# RMP_-_HALF_BRIDGE_0_0_2.net
KiCad netlist of a schematic drawn in EAGLE
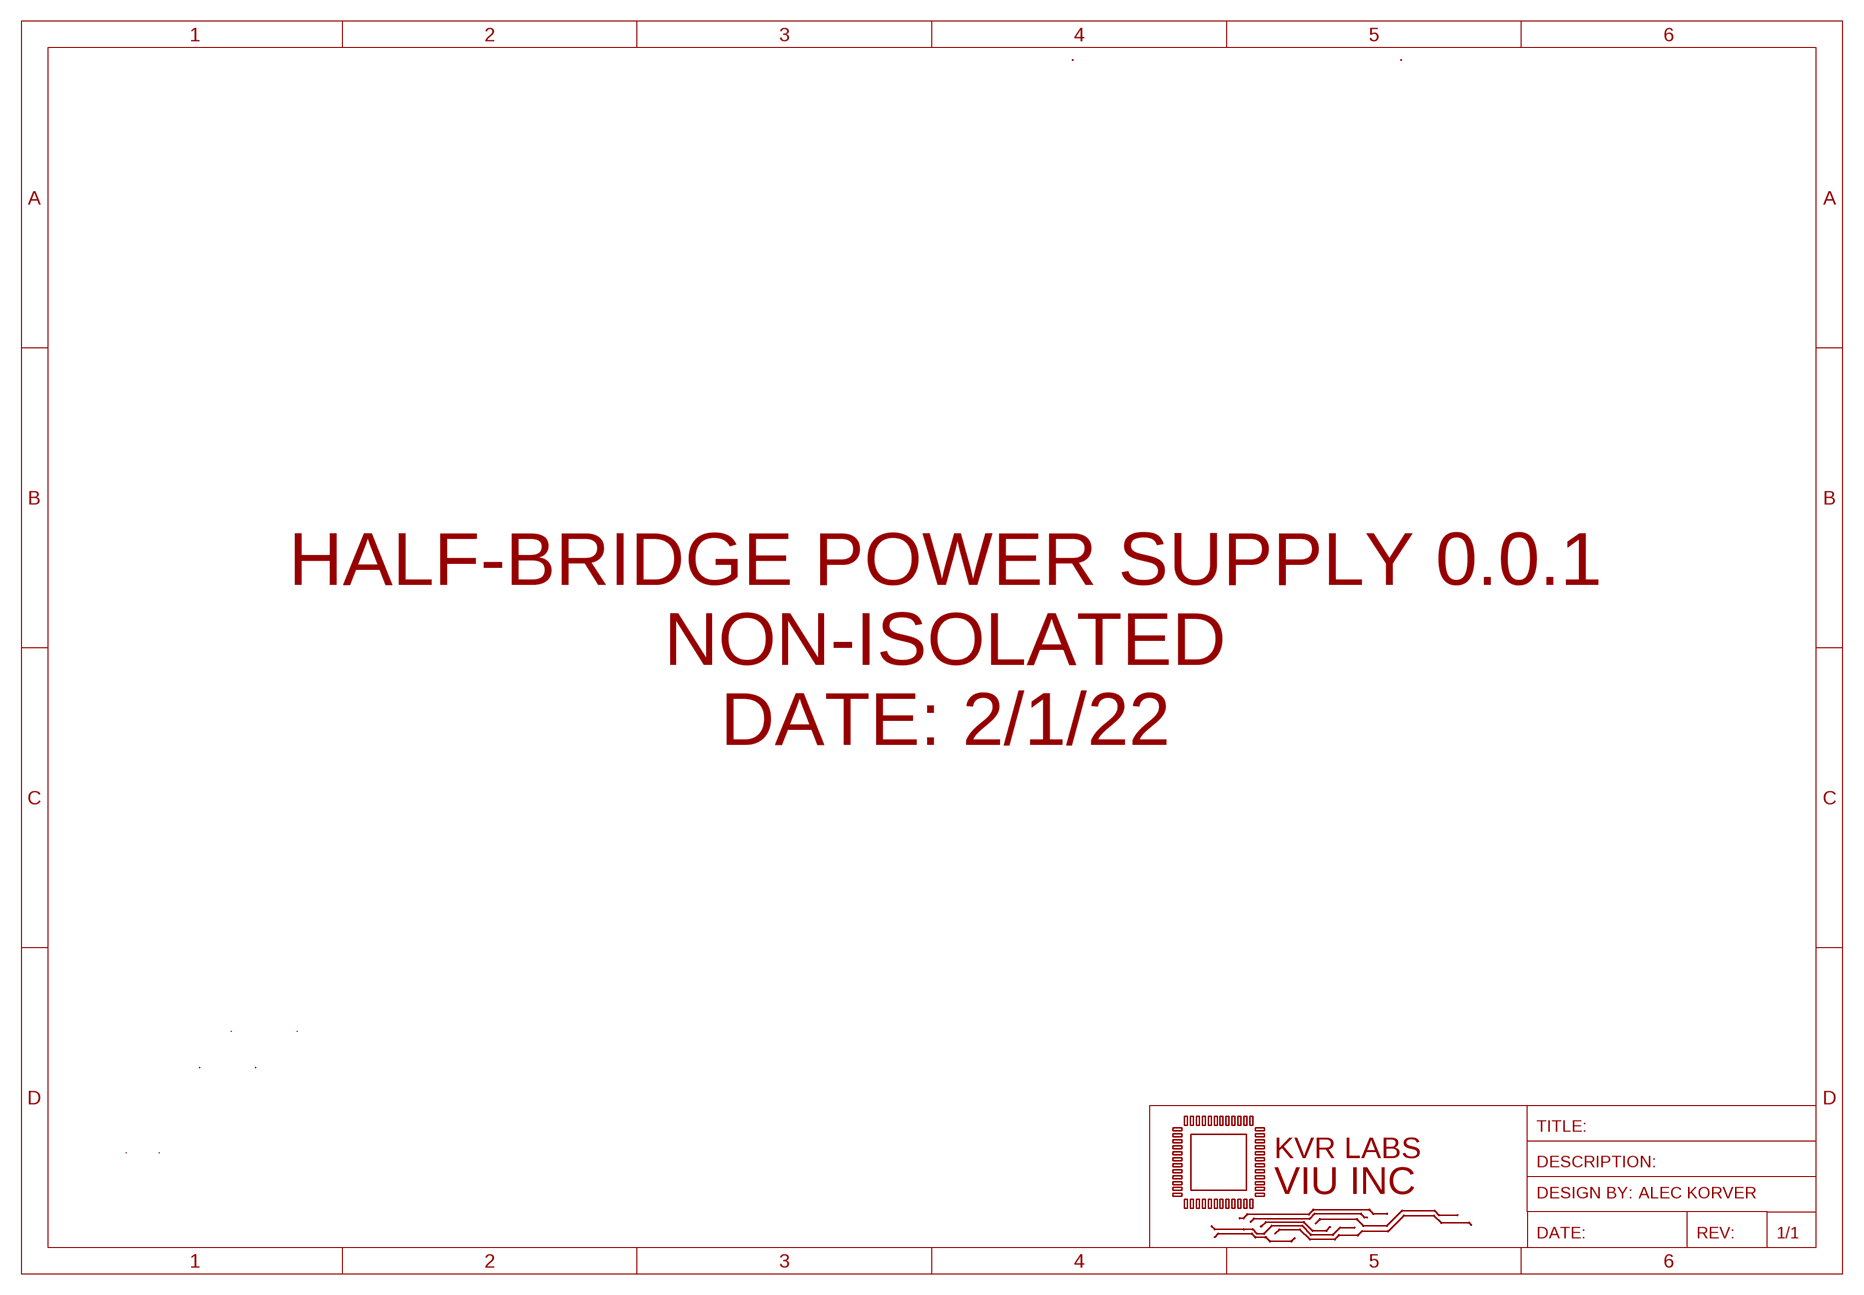
[diagram p0: schematic, sheet 1]
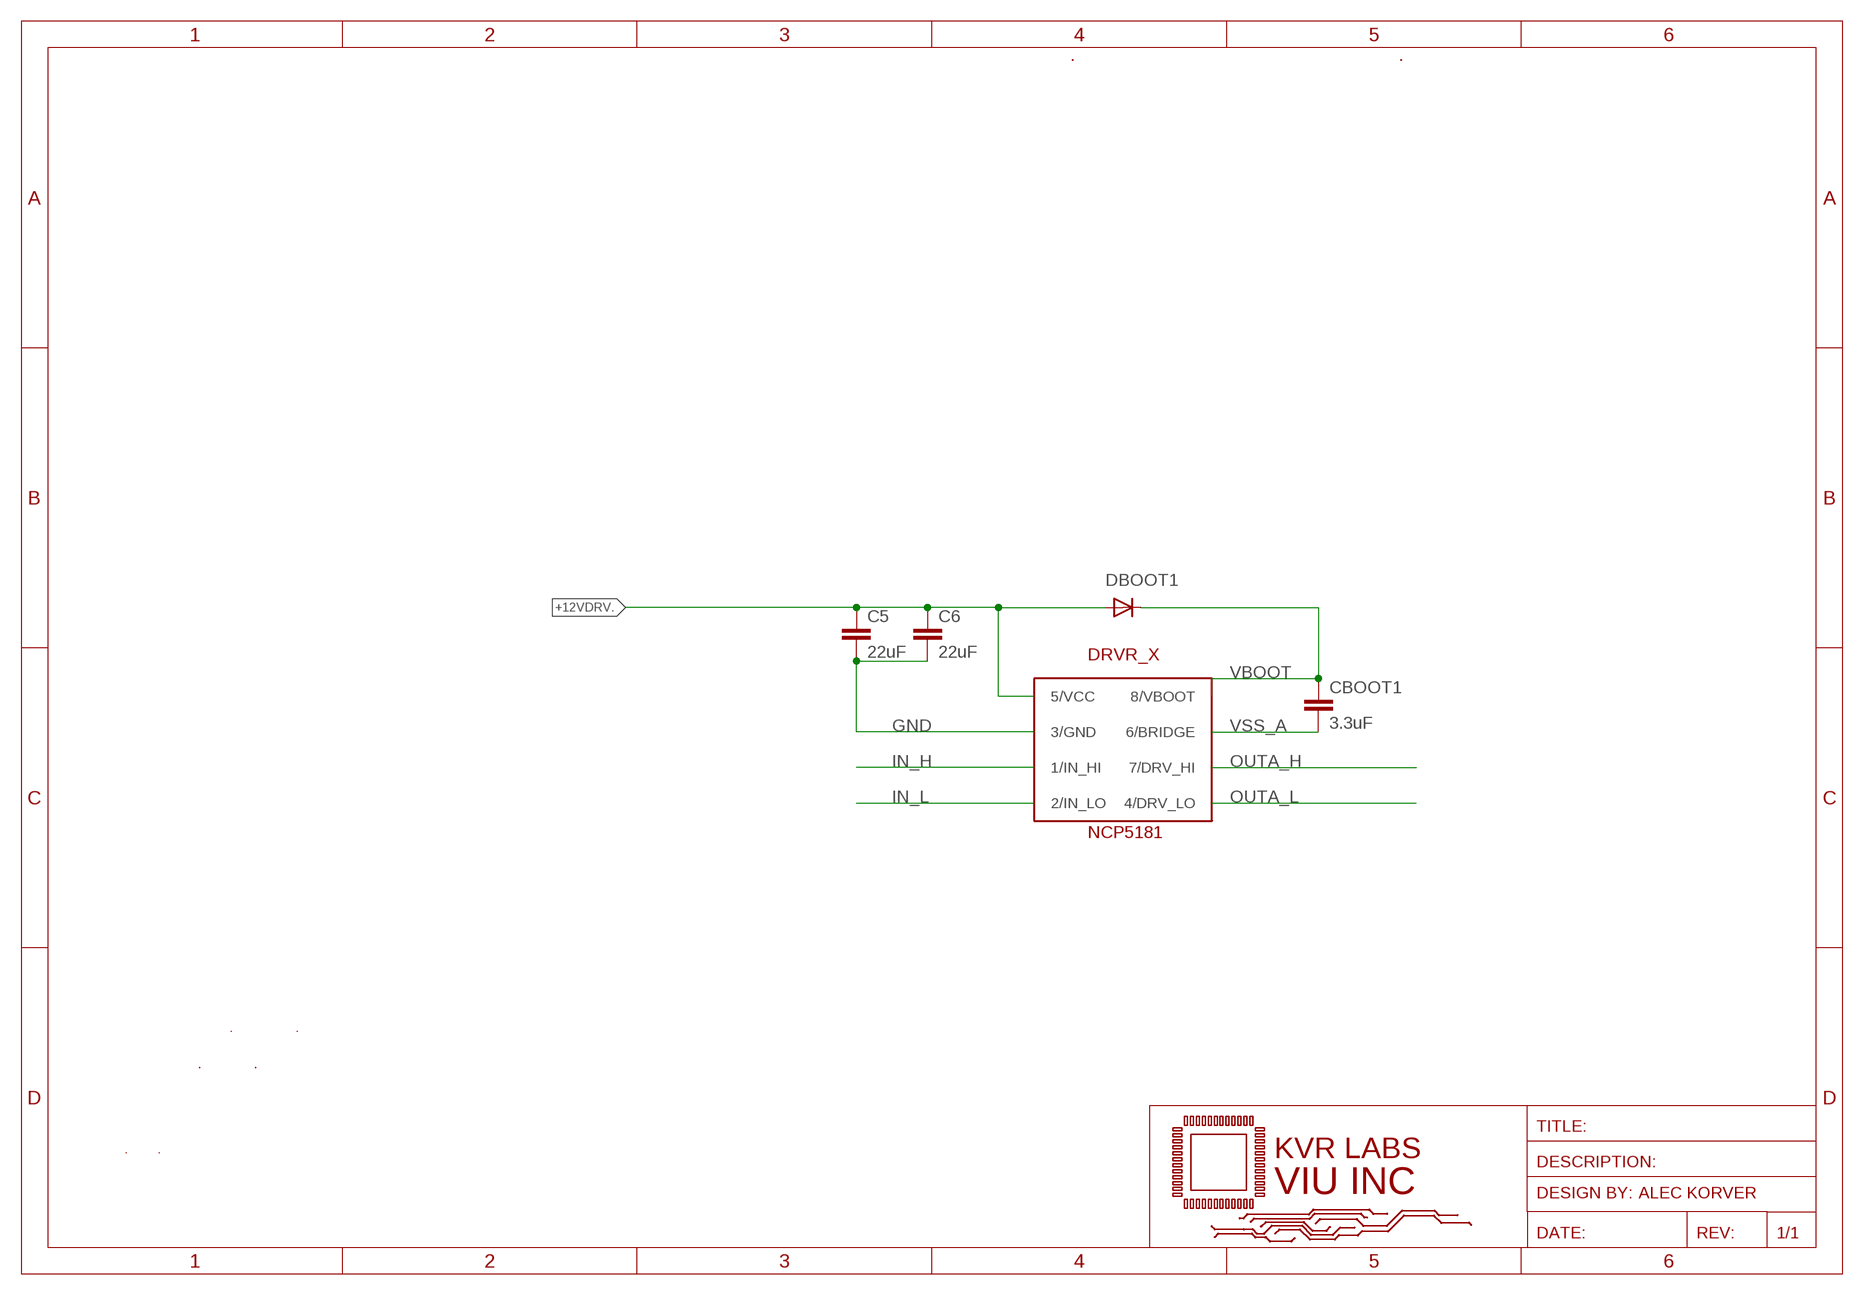
[diagram p1: schematic, sheet 2]
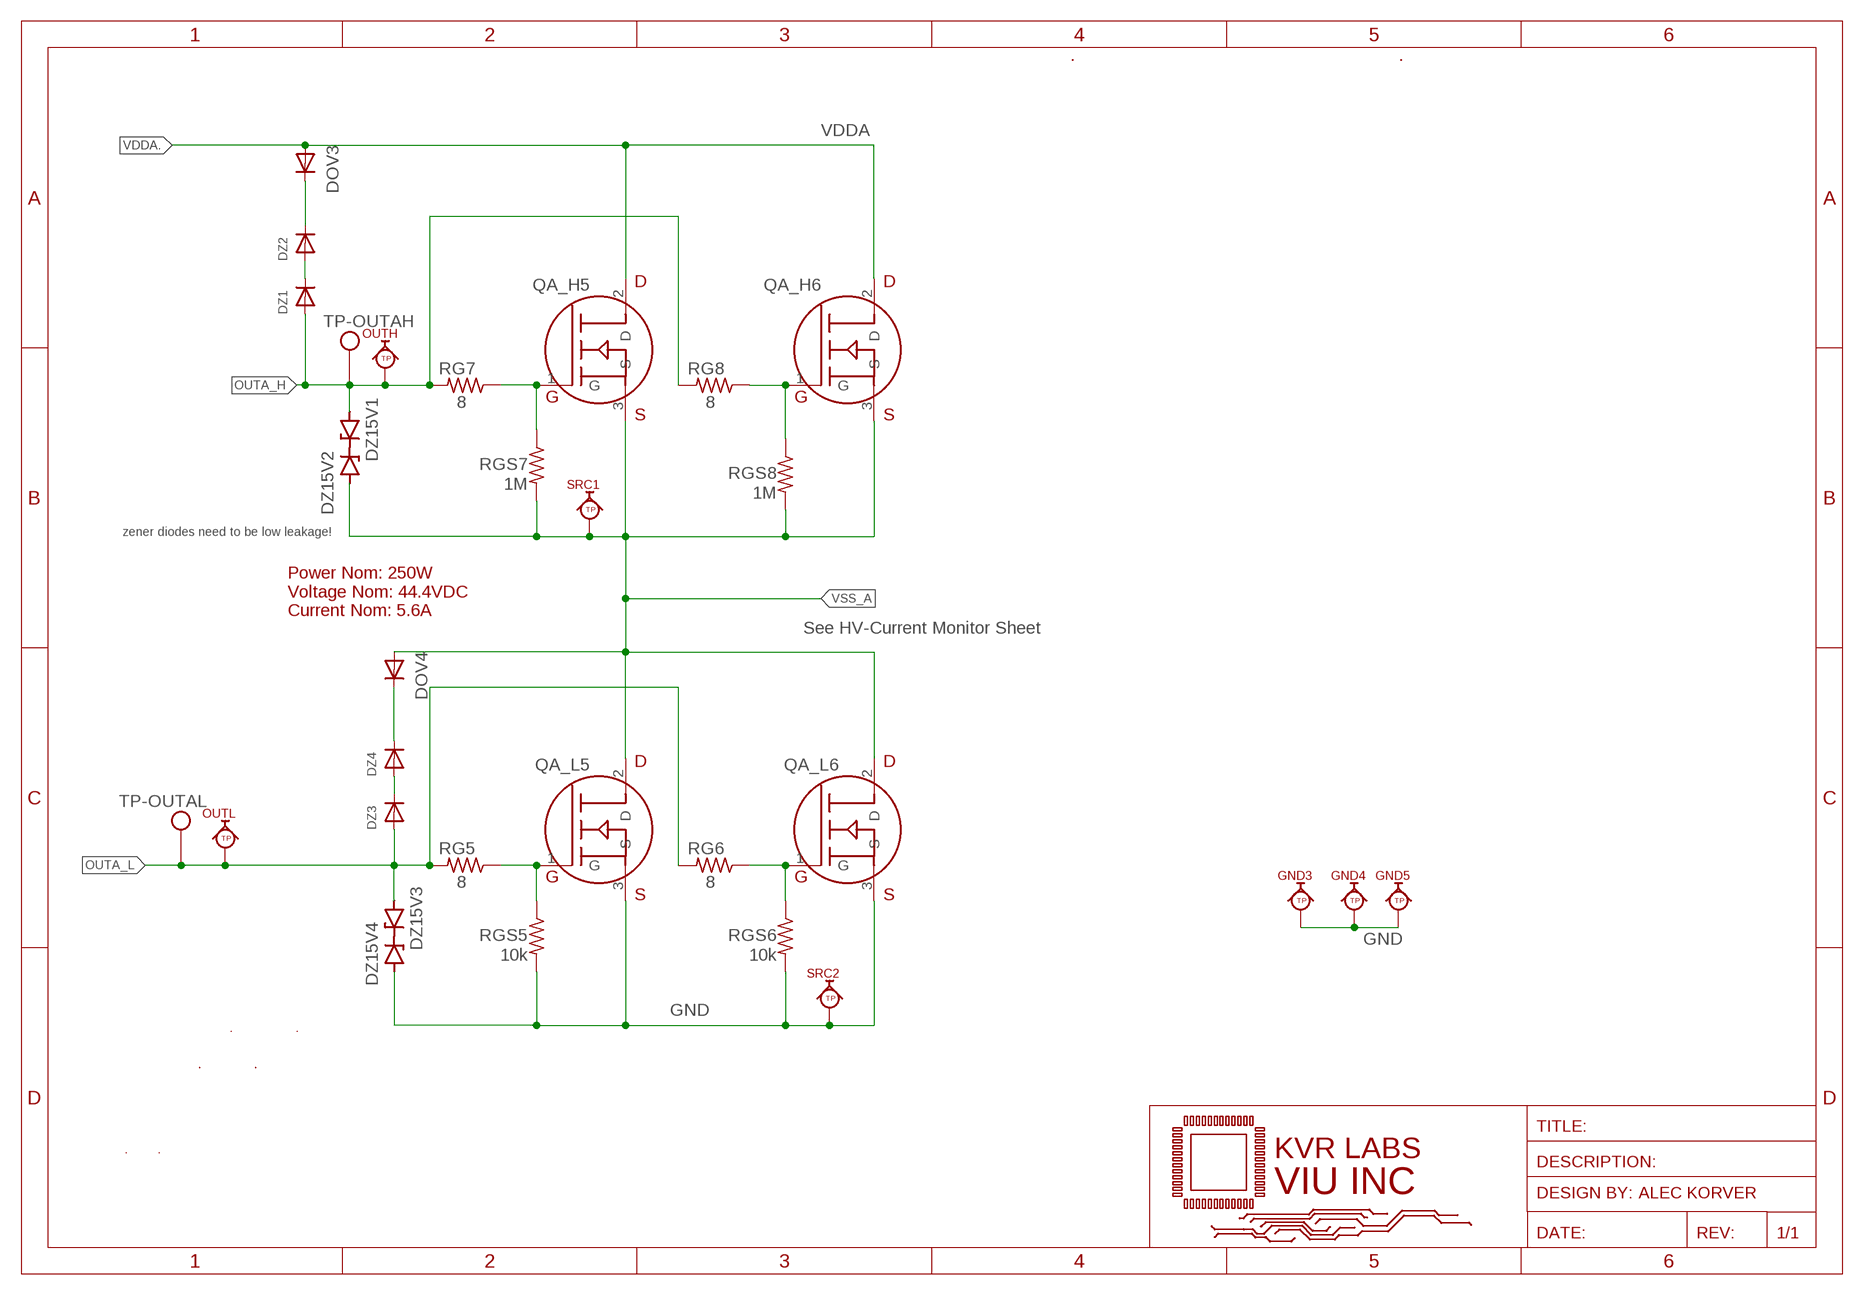
[diagram p2: schematic, sheet 3]
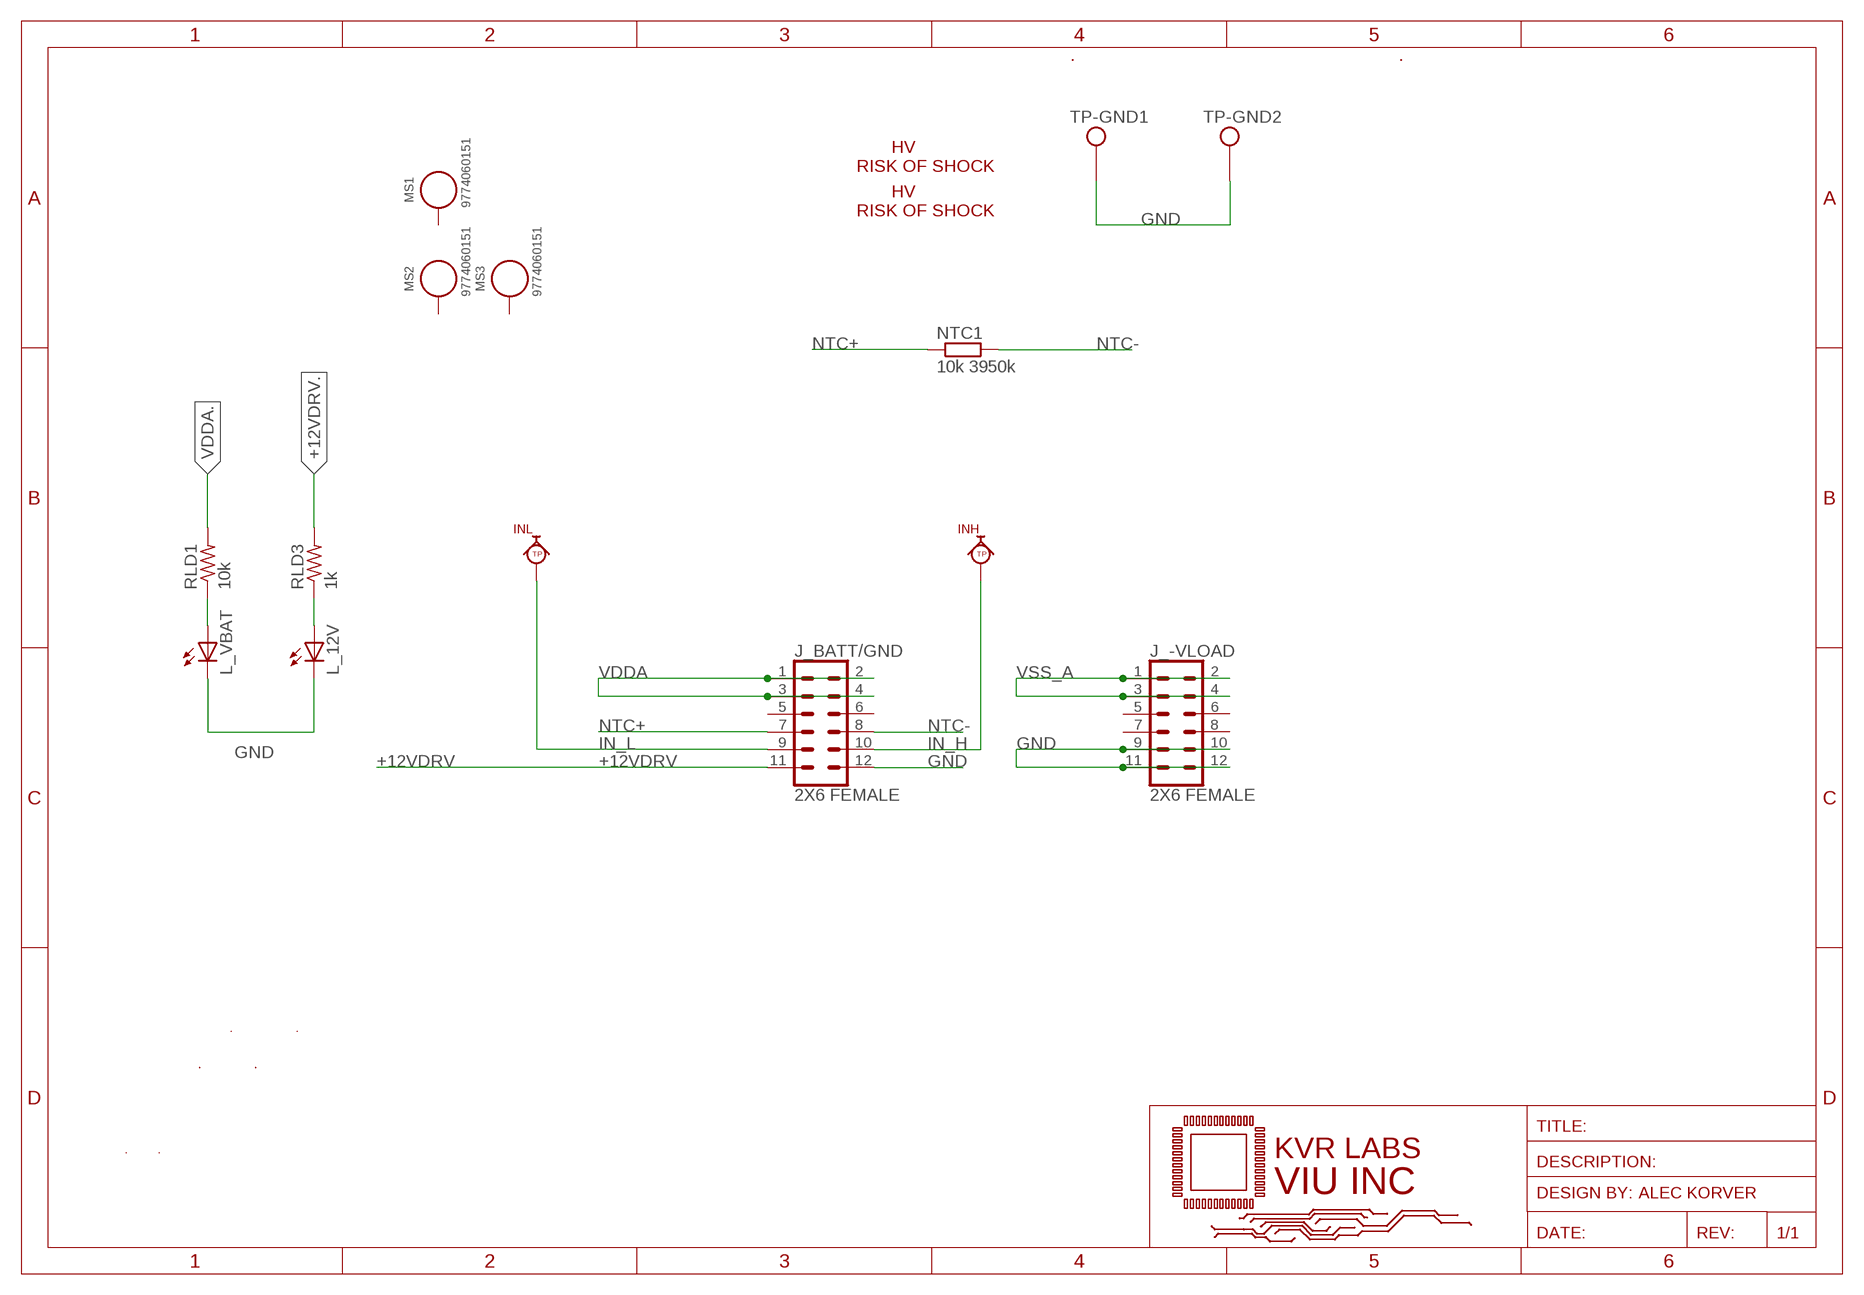
[diagram p3: schematic, sheet 4]
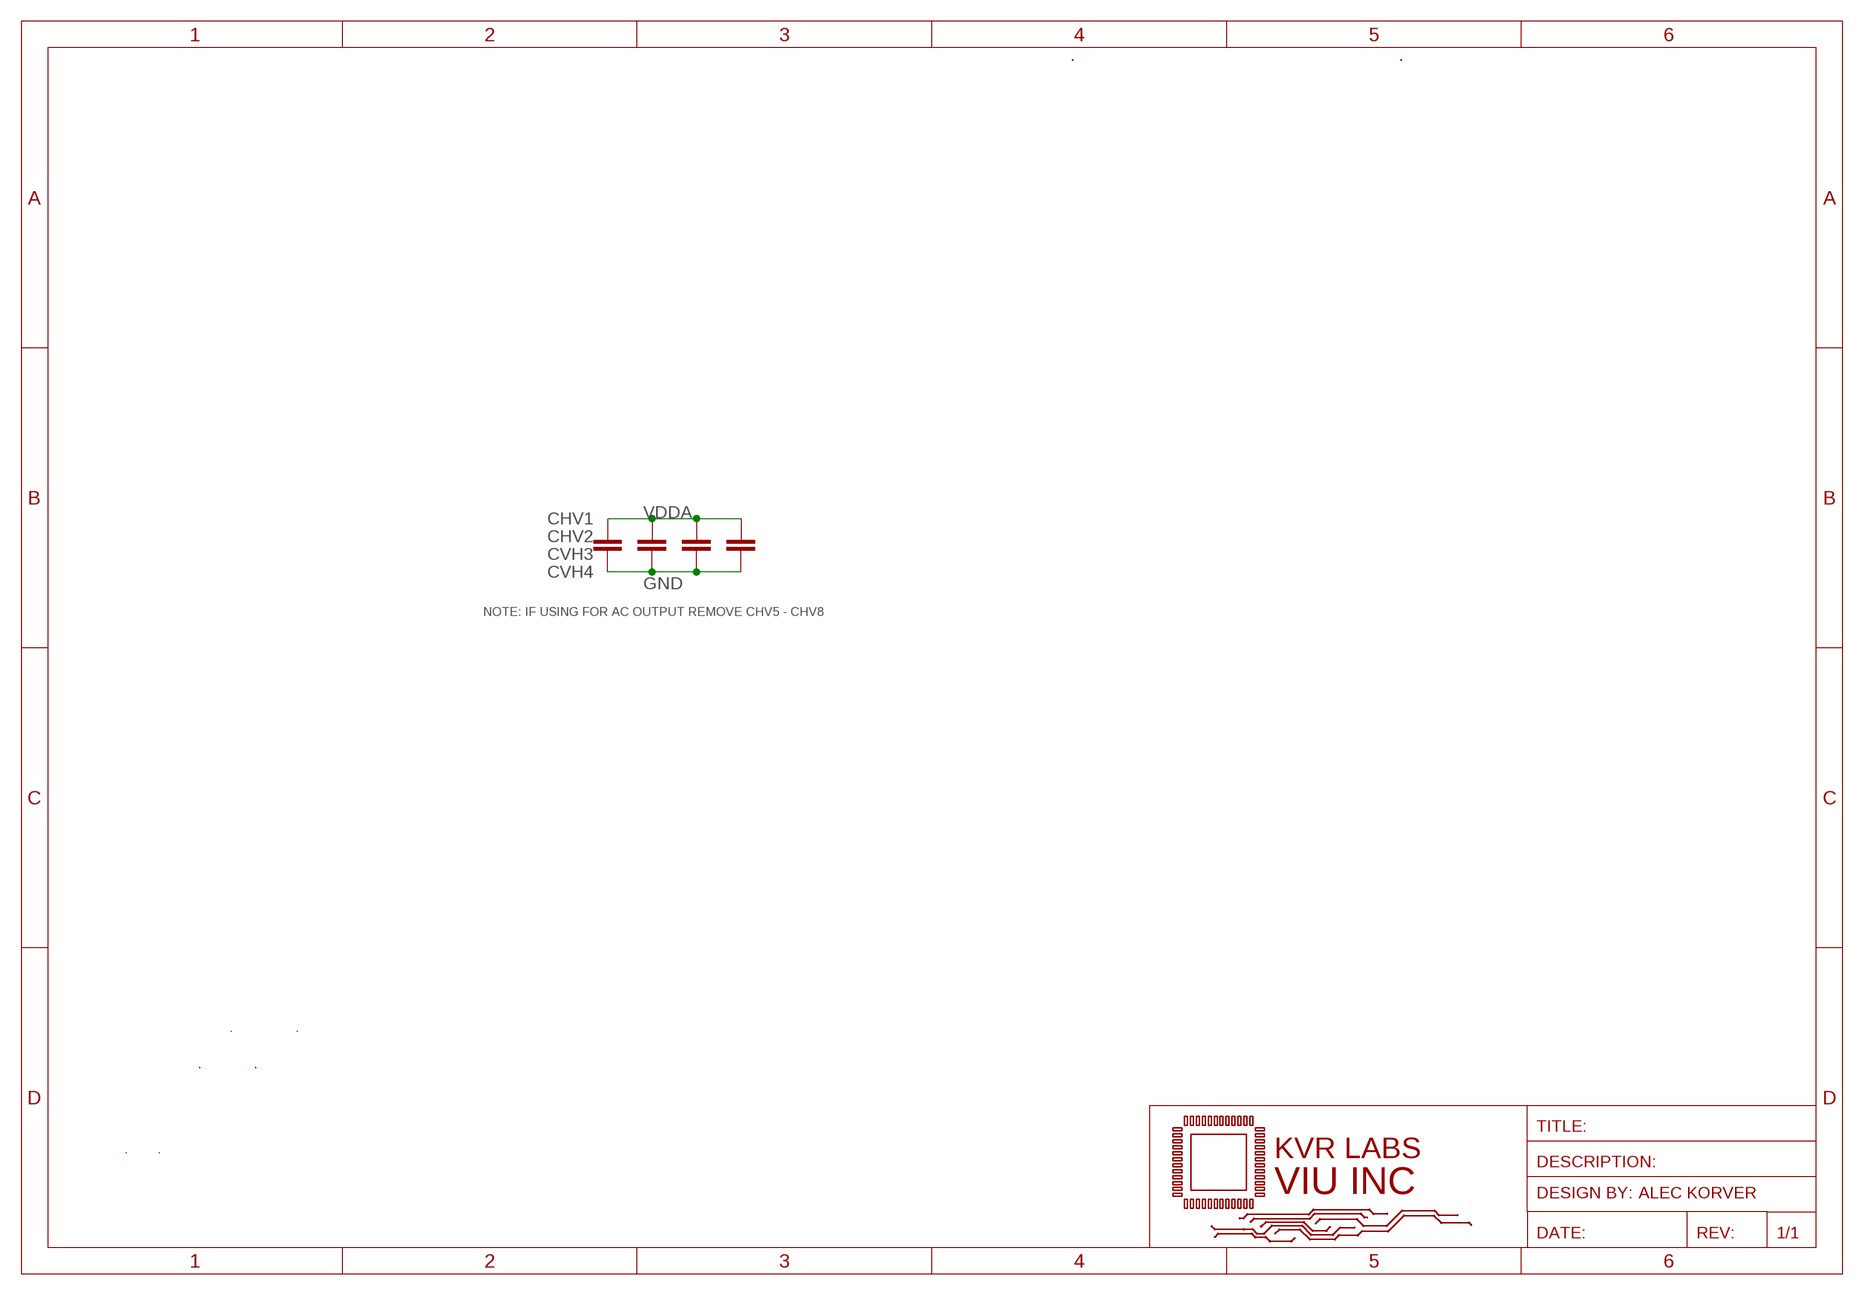
[diagram p4: schematic, sheet 5]

(export (version "E")
  (design (tool "Eeschema 10.0.6"))
  (components
    (comp (ref "CHV1")
      (value "3.3uF, 100V")
      (footprint "eagle-import:C2220K")
      (fields (field (name "LCSC_PART") "DNP/C342270"))
      (libsource (lib "eagle-import") (part "C-EUC2220K"))
    )
    (comp (ref "CHV2")
      (value "3.3uF, 100V")
      (footprint "eagle-import:C2220K")
      (fields (field (name "LCSC_PART") "DNP/C342270"))
      (libsource (lib "eagle-import") (part "C-EUC2220K"))
    )
    (comp (ref "CVH3")
      (value "3.3uF, 100V")
      (footprint "eagle-import:C2220K")
      (fields (field (name "LCSC_PART") "DNP/C342270"))
      (libsource (lib "eagle-import") (part "C-EUC2220K"))
    )
    (comp (ref "CVH4")
      (value "3.3uF, 100V")
      (footprint "eagle-import:C2220K")
      (fields (field (name "LCSC_PART") "DNP/C342270"))
      (libsource (lib "eagle-import") (part "C-EUC2220K"))
    )
    (comp (ref "INH")
      (value "KEYSTONE_5190_SMT")
      (footprint "eagle-import:KEYSTONE_5190_SMT")
      (libsource (lib "eagle-import") (part "KEYSTONE_5190_SMT"))
    )
    (comp (ref "INL")
      (value "KEYSTONE_5190_SMT")
      (footprint "eagle-import:KEYSTONE_5190_SMT")
      (libsource (lib "eagle-import") (part "KEYSTONE_5190_SMT"))
    )
    (comp (ref "J_-VLOAD")
      (value "2X6 FEMALE")
      (footprint "eagle-import:2X6")
      (fields (field (name "LCSC_PART") "DNP"))
      (libsource (lib "eagle-import") (part "CONN_06X2PTH_FEMALE"))
    )
    (comp (ref "J_BATT/GND")
      (value "2X6 FEMALE")
      (footprint "eagle-import:2X6")
      (fields (field (name "LCSC_PART") "DNP"))
      (libsource (lib "eagle-import") (part "CONN_06X2PTH_FEMALE"))
    )
    (comp (ref "L_12V")
      (value "LEDCHIPLED_1206")
      (footprint "eagle-import:CHIPLED_1206")
      (fields (field (name "LCSC_PART") "C434439"))
      (libsource (lib "eagle-import") (part "LEDCHIPLED_1206"))
    )
    (comp (ref "L_VBAT")
      (value "LEDCHIPLED_1206")
      (footprint "eagle-import:CHIPLED_1206")
      (fields (field (name "LCSC_PART") "C434439"))
      (libsource (lib "eagle-import") (part "LEDCHIPLED_1206"))
    )
    (comp (ref "MS1")
      (value "9774060151")
      (footprint "eagle-import:WA-SMSI_9774060151")
      (fields (field (name "LCSC_PART") "DNP"))
      (libsource (lib "eagle-import") (part "WA-SMSI_9774XXX151_9774060151"))
    )
    (comp (ref "MS2")
      (value "9774060151")
      (footprint "eagle-import:WA-SMSI_9774060151")
      (fields (field (name "LCSC_PART") "DNP"))
      (libsource (lib "eagle-import") (part "WA-SMSI_9774XXX151_9774060151"))
    )
    (comp (ref "MS3")
      (value "9774060151")
      (footprint "eagle-import:WA-SMSI_9774060151")
      (fields (field (name "LCSC_PART") "DNP"))
      (libsource (lib "eagle-import") (part "WA-SMSI_9774XXX151_9774060151"))
    )
    (comp (ref "NTC1")
      (value "10k 3950k")
      (footprint "eagle-import:R0805")
      (fields (field (name "LCSC_PART") "C95968"))
      (libsource (lib "eagle-import") (part "R-EU_R0805"))
    )
    (comp (ref "RLD1")
      (value "10k")
      (footprint "eagle-import:R1206")
      (fields (field (name "LCSC_PART") "C140407"))
      (libsource (lib "eagle-import") (part "R-US_R1206"))
    )
    (comp (ref "RLD3")
      (value "1k")
      (footprint "eagle-import:R1206")
      (fields (field (name "LCSC_PART") "C115421"))
      (libsource (lib "eagle-import") (part "R-US_R1206"))
    )
    (comp (ref "TP-GND1")
      (value "THM_TESTPOINT_5000_SERIES")
      (footprint "eagle-import:THM-TESTPOINT")
      (fields (field (name "LCSC_PART") "DNP"))
      (libsource (lib "eagle-import") (part "THM_TESTPOINT_5000_SERIES"))
    )
    (comp (ref "TP-GND2")
      (value "THM_TESTPOINT_5000_SERIES")
      (footprint "eagle-import:THM-TESTPOINT")
      (fields (field (name "LCSC_PART") "DNP"))
      (libsource (lib "eagle-import") (part "THM_TESTPOINT_5000_SERIES"))
    )
    (comp (ref "U$10")
      (value "ELECTRIC_SHOCK")
      (footprint "eagle-import:ELECTRIC_SHOCK")
      (fields (field (name "LCSC_PART") "DNP"))
      (libsource (lib "eagle-import") (part "ELECTRIC_SHOCK"))
    )
    (comp (ref "U$11")
      (value "ELECTRIC_SHOCK")
      (footprint "eagle-import:ELECTRIC_SHOCK")
      (fields (field (name "LCSC_PART") "DNP"))
      (libsource (lib "eagle-import") (part "ELECTRIC_SHOCK"))
    )
    (comp (ref "C5")
      (value "22uF")
      (footprint "eagle-import:C1206")
      (fields (field (name "LCSC_PART") "C77091"))
      (libsource (lib "eagle-import") (part "C-EUC1206"))
    )
    (comp (ref "C6")
      (value "22uF")
      (footprint "eagle-import:C1206")
      (fields (field (name "LCSC_PART") "C77091"))
      (libsource (lib "eagle-import") (part "C-EUC1206"))
    )
    (comp (ref "CBOOT1")
      (value "3.3uF")
      (footprint "eagle-import:C1812")
      (fields (field (name "LCSC_PART") "C342636"))
      (libsource (lib "eagle-import") (part "C-EUC1812"))
    )
    (comp (ref "DBOOT1")
      (value "DIODESMA")
      (footprint "eagle-import:SMADIODE")
      (fields (field (name "LCSC_PART") "C110531"))
      (libsource (lib "eagle-import") (part "DIODESMA"))
    )
    (comp (ref "DRVR_X")
      (value "NCP5181")
      (footprint "eagle-import:8-SOIC")
      (fields (field (name "LCSC_PART") "DNP"))
      (libsource (lib "eagle-import") (part "NCP5181"))
    )
    (comp (ref "DOV3")
      (value "DIODESMA")
      (footprint "eagle-import:SMADIODE")
      (fields (field (name "LCSC_PART") "C110531"))
      (libsource (lib "eagle-import") (part "DIODESMA"))
    )
    (comp (ref "DOV4")
      (value "DIODESMA")
      (footprint "eagle-import:SMADIODE")
      (fields (field (name "LCSC_PART") "C110531"))
      (libsource (lib "eagle-import") (part "DIODESMA"))
    )
    (comp (ref "DZ1")
      (value "DIODESMA")
      (footprint "eagle-import:SMADIODE")
      (fields (field (name "LCSC_PART") "C362303"))
      (libsource (lib "eagle-import") (part "DIODESMA"))
    )
    (comp (ref "DZ2")
      (value "DIODESMA")
      (footprint "eagle-import:SMADIODE")
      (fields (field (name "LCSC_PART") "C362303"))
      (libsource (lib "eagle-import") (part "DIODESMA"))
    )
    (comp (ref "DZ3")
      (value "DIODESMA")
      (footprint "eagle-import:SMADIODE")
      (fields (field (name "LCSC_PART") "C362303"))
      (libsource (lib "eagle-import") (part "DIODESMA"))
    )
    (comp (ref "DZ4")
      (value "DIODESMA")
      (footprint "eagle-import:SMADIODE")
      (fields (field (name "LCSC_PART") "C362303"))
      (libsource (lib "eagle-import") (part "DIODESMA"))
    )
    (comp (ref "DZ15V1")
      (value "NZH15B,115")
      (footprint "eagle-import:SODFL3718X115")
      (fields
        (field (name "MANUFACTURER") "ON Semiconductor ")
        (field (name "MPN") "MMSZ5240BT1G")
        (field (name "LCSC_PART") "C173428")
      )
      (libsource (lib "eagle-import") (part "ZENER_DO-219-AB(SOD123F)MMSZ5240BT"))
    )
    (comp (ref "DZ15V2")
      (value "NZH15B,115")
      (footprint "eagle-import:SODFL3718X115")
      (fields
        (field (name "MANUFACTURER") "ON Semiconductor ")
        (field (name "MPN") "MMSZ5240BT1G")
        (field (name "LCSC_PART") "C173428")
      )
      (libsource (lib "eagle-import") (part "ZENER_DO-219-AB(SOD123F)MMSZ5240BT"))
    )
    (comp (ref "DZ15V3")
      (value "NZH15B,115")
      (footprint "eagle-import:SODFL3718X115")
      (fields
        (field (name "MANUFACTURER") "ON Semiconductor ")
        (field (name "MPN") "MMSZ5240BT1G")
        (field (name "LCSC_PART") "C173428")
      )
      (libsource (lib "eagle-import") (part "ZENER_DO-219-AB(SOD123F)MMSZ5240BT"))
    )
    (comp (ref "DZ15V4")
      (value "NZH15B,115")
      (footprint "eagle-import:SODFL3718X115")
      (fields
        (field (name "MANUFACTURER") "ON Semiconductor ")
        (field (name "MPN") "MMSZ5240BT1G")
        (field (name "LCSC_PART") "C173428")
      )
      (libsource (lib "eagle-import") (part "ZENER_DO-219-AB(SOD123F)MMSZ5240BT"))
    )
    (comp (ref "GND3")
      (value "KEYSTONE_5190_SMT")
      (footprint "eagle-import:KEYSTONE_5190_SMT")
      (libsource (lib "eagle-import") (part "KEYSTONE_5190_SMT"))
    )
    (comp (ref "GND4")
      (value "KEYSTONE_5190_SMT")
      (footprint "eagle-import:KEYSTONE_5190_SMT")
      (libsource (lib "eagle-import") (part "KEYSTONE_5190_SMT"))
    )
    (comp (ref "GND5")
      (value "KEYSTONE_5190_SMT")
      (footprint "eagle-import:KEYSTONE_5190_SMT")
      (libsource (lib "eagle-import") (part "KEYSTONE_5190_SMT"))
    )
    (comp (ref "OUTH")
      (value "KEYSTONE_5190_SMT")
      (footprint "eagle-import:KEYSTONE_5190_SMT")
      (libsource (lib "eagle-import") (part "KEYSTONE_5190_SMT"))
    )
    (comp (ref "OUTL")
      (value "KEYSTONE_5190_SMT")
      (footprint "eagle-import:KEYSTONE_5190_SMT")
      (libsource (lib "eagle-import") (part "KEYSTONE_5190_SMT"))
    )
    (comp (ref "QA_H5")
      (value "IPB60R060P7ATMA1")
      (footprint "eagle-import:D2PACK")
      (fields (field (name "LCSC_PART") "C604524"))
      (libsource (lib "eagle-import") (part "IPB60R060P7ATMA1"))
    )
    (comp (ref "QA_H6")
      (value "IPB60R060P7ATMA1")
      (footprint "eagle-import:D2PACK")
      (fields (field (name "LCSC_PART") "C604524"))
      (libsource (lib "eagle-import") (part "IPB60R060P7ATMA1"))
    )
    (comp (ref "QA_L5")
      (value "IPB60R060P7ATMA1")
      (footprint "eagle-import:D2PACK")
      (fields (field (name "LCSC_PART") "C604524"))
      (libsource (lib "eagle-import") (part "IPB60R060P7ATMA1"))
    )
    (comp (ref "QA_L6")
      (value "IPB60R060P7ATMA1")
      (footprint "eagle-import:D2PACK")
      (fields (field (name "LCSC_PART") "C604524"))
      (libsource (lib "eagle-import") (part "IPB60R060P7ATMA1"))
    )
    (comp (ref "RG5")
      (value "8")
      (footprint "eagle-import:R1206")
      (fields (field (name "LCSC_PART") "C118070"))
      (libsource (lib "eagle-import") (part "R-US_R1206"))
    )
    (comp (ref "RG6")
      (value "8")
      (footprint "eagle-import:R1206")
      (fields (field (name "LCSC_PART") "C118070"))
      (libsource (lib "eagle-import") (part "R-US_R1206"))
    )
    (comp (ref "RG7")
      (value "8")
      (footprint "eagle-import:R1206")
      (fields (field (name "LCSC_PART") "C118070"))
      (libsource (lib "eagle-import") (part "R-US_R1206"))
    )
    (comp (ref "RG8")
      (value "8")
      (footprint "eagle-import:R1206")
      (fields (field (name "LCSC_PART") "C118070"))
      (libsource (lib "eagle-import") (part "R-US_R1206"))
    )
    (comp (ref "RGS5")
      (value "10k")
      (footprint "eagle-import:R1206")
      (fields (field (name "LCSC_PART") "C140407"))
      (libsource (lib "eagle-import") (part "R-US_R1206"))
    )
    (comp (ref "RGS6")
      (value "10k")
      (footprint "eagle-import:R1206")
      (fields (field (name "LCSC_PART") "C140407"))
      (libsource (lib "eagle-import") (part "R-US_R1206"))
    )
    (comp (ref "RGS7")
      (value "1M")
      (footprint "eagle-import:R1206")
      (fields (field (name "LCSC_PART") "C105578"))
      (libsource (lib "eagle-import") (part "R-US_R1206"))
    )
    (comp (ref "RGS8")
      (value "1M")
      (footprint "eagle-import:R1206")
      (fields (field (name "LCSC_PART") "C105578"))
      (libsource (lib "eagle-import") (part "R-US_R1206"))
    )
    (comp (ref "SRC1")
      (value "KEYSTONE_5190_SMT")
      (footprint "eagle-import:KEYSTONE_5190_SMT")
      (libsource (lib "eagle-import") (part "KEYSTONE_5190_SMT"))
    )
    (comp (ref "SRC2")
      (value "KEYSTONE_5190_SMT")
      (footprint "eagle-import:KEYSTONE_5190_SMT")
      (libsource (lib "eagle-import") (part "KEYSTONE_5190_SMT"))
    )
    (comp (ref "TP-OUTAH")
      (value "THM_TESTPOINT_5000_SERIES")
      (footprint "eagle-import:THM-TESTPOINT")
      (fields (field (name "LCSC_PART") "DNP"))
      (libsource (lib "eagle-import") (part "THM_TESTPOINT_5000_SERIES"))
    )
    (comp (ref "TP-OUTAL")
      (value "THM_TESTPOINT_5000_SERIES")
      (footprint "eagle-import:THM-TESTPOINT")
      (fields (field (name "LCSC_PART") "DNP"))
      (libsource (lib "eagle-import") (part "THM_TESTPOINT_5000_SERIES"))
    )
  )
  (nets
    (net (code "1") (name "+12VDRV") (class "Default")
      (node (ref "C5") (pin "1") (pinfunction "1_1") (pintype "passive"))
      (node (ref "C6") (pin "1") (pinfunction "1_1") (pintype "passive"))
      (node (ref "DBOOT1") (pin "A") (pinfunction "A_A") (pintype "passive"))
      (node (ref "DRVR_X") (pin "5") (pinfunction "5/VCC_5") (pintype "bidirectional"))
      (node (ref "J_BATT/GND") (pin "11") (pinfunction "11_11") (pintype "passive"))
      (node (ref "RLD3") (pin "2") (pinfunction "2_2") (pintype "passive"))
    )
    (net (code "2") (name "GND") (class "Default")
      (node (ref "C5") (pin "2") (pinfunction "2_2") (pintype "passive"))
      (node (ref "C6") (pin "2") (pinfunction "2_2") (pintype "passive"))
      (node (ref "CHV1") (pin "2") (pinfunction "2_2") (pintype "passive"))
      (node (ref "CHV2") (pin "2") (pinfunction "2_2") (pintype "passive"))
      (node (ref "CVH3") (pin "2") (pinfunction "2_2") (pintype "passive"))
      (node (ref "CVH4") (pin "2") (pinfunction "2_2") (pintype "passive"))
      (node (ref "DRVR_X") (pin "3") (pinfunction "3/GND_3") (pintype "bidirectional"))
      (node (ref "DZ15V4") (pin "2") (pinfunction "A_2") (pintype "passive"))
      (node (ref "GND3") (pin "P$1") (pinfunction "P$1_P$1") (pintype "bidirectional"))
      (node (ref "GND4") (pin "P$1") (pinfunction "P$1_P$1") (pintype "bidirectional"))
      (node (ref "GND5") (pin "P$1") (pinfunction "P$1_P$1") (pintype "bidirectional"))
      (node (ref "J_-VLOAD") (pin "10") (pinfunction "10_10") (pintype "passive"))
      (node (ref "J_-VLOAD") (pin "11") (pinfunction "11_11") (pintype "passive"))
      (node (ref "J_-VLOAD") (pin "12") (pinfunction "12_12") (pintype "passive"))
      (node (ref "J_-VLOAD") (pin "9") (pinfunction "9_9") (pintype "passive"))
      (node (ref "J_BATT/GND") (pin "12") (pinfunction "12_12") (pintype "passive"))
      (node (ref "L_12V") (pin "C") (pinfunction "C_C") (pintype "passive"))
      (node (ref "L_VBAT") (pin "C") (pinfunction "C_C") (pintype "passive"))
      (node (ref "QA_L5") (pin "3") (pinfunction "S_3") (pintype "bidirectional"))
      (node (ref "QA_L6") (pin "3") (pinfunction "S_3") (pintype "bidirectional"))
      (node (ref "RGS5") (pin "2") (pinfunction "2_2") (pintype "passive"))
      (node (ref "RGS6") (pin "2") (pinfunction "2_2") (pintype "passive"))
      (node (ref "SRC2") (pin "P$1") (pinfunction "P$1_P$1") (pintype "bidirectional"))
      (node (ref "TP-GND1") (pin "P1") (pinfunction "P$1_P1") (pintype "bidirectional"))
      (node (ref "TP-GND2") (pin "P1") (pinfunction "P$1_P1") (pintype "bidirectional"))
    )
    (net (code "3") (name "IN_H") (class "Default")
      (node (ref "DRVR_X") (pin "1") (pinfunction "1/IN_HI_1") (pintype "bidirectional"))
      (node (ref "INH") (pin "P$1") (pinfunction "P$1_P$1") (pintype "bidirectional"))
      (node (ref "J_BATT/GND") (pin "10") (pinfunction "10_10") (pintype "passive"))
    )
    (net (code "4") (name "IN_L") (class "Default")
      (node (ref "DRVR_X") (pin "2") (pinfunction "2/IN_LO_2") (pintype "bidirectional"))
      (node (ref "INL") (pin "P$1") (pinfunction "P$1_P$1") (pintype "bidirectional"))
      (node (ref "J_BATT/GND") (pin "9") (pinfunction "9_9") (pintype "passive"))
    )
    (net (code "5") (name "NTC+") (class "Default")
      (node (ref "J_BATT/GND") (pin "7") (pinfunction "7_7") (pintype "passive"))
      (node (ref "NTC1") (pin "1") (pinfunction "1_1") (pintype "passive"))
    )
    (net (code "6") (name "NTC-") (class "Default")
      (node (ref "J_BATT/GND") (pin "8") (pinfunction "8_8") (pintype "passive"))
      (node (ref "NTC1") (pin "2") (pinfunction "2_2") (pintype "passive"))
    )
    (net (code "7") (name "Net-(DOV3-PadC)") (class "Default")
      (node (ref "DOV3") (pin "C") (pinfunction "C_C") (pintype "passive"))
      (node (ref "DZ2") (pin "C") (pinfunction "C_C") (pintype "passive"))
    )
    (net (code "8") (name "Net-(DOV4-PadC)") (class "Default")
      (node (ref "DOV4") (pin "C") (pinfunction "C_C") (pintype "passive"))
      (node (ref "DZ4") (pin "C") (pinfunction "C_C") (pintype "passive"))
    )
    (net (code "9") (name "Net-(DZ1-PadC)") (class "Default")
      (node (ref "DZ1") (pin "C") (pinfunction "C_C") (pintype "passive"))
      (node (ref "DZ2") (pin "A") (pinfunction "A_A") (pintype "passive"))
    )
    (net (code "10") (name "Net-(DZ3-PadC)") (class "Default")
      (node (ref "DZ3") (pin "C") (pinfunction "C_C") (pintype "passive"))
      (node (ref "DZ4") (pin "A") (pinfunction "A_A") (pintype "passive"))
    )
    (net (code "11") (name "Net-(DZ15V1-C)") (class "Default")
      (node (ref "DZ15V1") (pin "1") (pinfunction "C_1") (pintype "passive"))
      (node (ref "DZ15V2") (pin "1") (pinfunction "C_1") (pintype "passive"))
    )
    (net (code "12") (name "Net-(DZ15V3-C)") (class "Default")
      (node (ref "DZ15V3") (pin "1") (pinfunction "C_1") (pintype "passive"))
      (node (ref "DZ15V4") (pin "1") (pinfunction "C_1") (pintype "passive"))
    )
    (net (code "13") (name "Net-(L_12V-PadA)") (class "Default")
      (node (ref "L_12V") (pin "A") (pinfunction "A_A") (pintype "passive"))
      (node (ref "RLD3") (pin "1") (pinfunction "1_1") (pintype "passive"))
    )
    (net (code "14") (name "Net-(L_VBAT-PadA)") (class "Default")
      (node (ref "L_VBAT") (pin "A") (pinfunction "A_A") (pintype "passive"))
      (node (ref "RLD1") (pin "1") (pinfunction "1_1") (pintype "passive"))
    )
    (net (code "15") (name "Net-(QA_H5-G)") (class "Default")
      (node (ref "QA_H5") (pin "1") (pinfunction "G_1") (pintype "bidirectional"))
      (node (ref "RG7") (pin "1") (pinfunction "1_1") (pintype "passive"))
      (node (ref "RGS7") (pin "1") (pinfunction "1_1") (pintype "passive"))
    )
    (net (code "16") (name "Net-(QA_H6-G)") (class "Default")
      (node (ref "QA_H6") (pin "1") (pinfunction "G_1") (pintype "bidirectional"))
      (node (ref "RG8") (pin "1") (pinfunction "1_1") (pintype "passive"))
      (node (ref "RGS8") (pin "1") (pinfunction "1_1") (pintype "passive"))
    )
    (net (code "17") (name "Net-(QA_L5-G)") (class "Default")
      (node (ref "QA_L5") (pin "1") (pinfunction "G_1") (pintype "bidirectional"))
      (node (ref "RG5") (pin "1") (pinfunction "1_1") (pintype "passive"))
      (node (ref "RGS5") (pin "1") (pinfunction "1_1") (pintype "passive"))
    )
    (net (code "18") (name "Net-(QA_L6-G)") (class "Default")
      (node (ref "QA_L6") (pin "1") (pinfunction "G_1") (pintype "bidirectional"))
      (node (ref "RG6") (pin "1") (pinfunction "1_1") (pintype "passive"))
      (node (ref "RGS6") (pin "1") (pinfunction "1_1") (pintype "passive"))
    )
    (net (code "19") (name "OUTA_H") (class "Default")
      (node (ref "DRVR_X") (pin "7") (pinfunction "7/DRV_HI_7") (pintype "bidirectional"))
      (node (ref "DZ1") (pin "A") (pinfunction "A_A") (pintype "passive"))
      (node (ref "DZ15V1") (pin "2") (pinfunction "A_2") (pintype "passive"))
      (node (ref "OUTH") (pin "P$1") (pinfunction "P$1_P$1") (pintype "bidirectional"))
      (node (ref "RG7") (pin "2") (pinfunction "2_2") (pintype "passive"))
      (node (ref "RG8") (pin "2") (pinfunction "2_2") (pintype "passive"))
      (node (ref "TP-OUTAH") (pin "P1") (pinfunction "P$1_P1") (pintype "bidirectional"))
    )
    (net (code "20") (name "OUTA_L") (class "Default")
      (node (ref "DRVR_X") (pin "4") (pinfunction "4/DRV_LO_4") (pintype "bidirectional"))
      (node (ref "DZ15V3") (pin "2") (pinfunction "A_2") (pintype "passive"))
      (node (ref "DZ3") (pin "A") (pinfunction "A_A") (pintype "passive"))
      (node (ref "OUTL") (pin "P$1") (pinfunction "P$1_P$1") (pintype "bidirectional"))
      (node (ref "RG5") (pin "2") (pinfunction "2_2") (pintype "passive"))
      (node (ref "RG6") (pin "2") (pinfunction "2_2") (pintype "passive"))
      (node (ref "TP-OUTAL") (pin "P1") (pinfunction "P$1_P1") (pintype "bidirectional"))
    )
    (net (code "21") (name "VBOOT") (class "Default")
      (node (ref "CBOOT1") (pin "1") (pinfunction "1_1") (pintype "passive"))
      (node (ref "DBOOT1") (pin "C") (pinfunction "C_C") (pintype "passive"))
      (node (ref "DRVR_X") (pin "8") (pinfunction "8/VBOOT_8") (pintype "bidirectional"))
    )
    (net (code "22") (name "VDDA") (class "Default")
      (node (ref "CHV1") (pin "1") (pinfunction "1_1") (pintype "passive"))
      (node (ref "CHV2") (pin "1") (pinfunction "1_1") (pintype "passive"))
      (node (ref "CVH3") (pin "1") (pinfunction "1_1") (pintype "passive"))
      (node (ref "CVH4") (pin "1") (pinfunction "1_1") (pintype "passive"))
      (node (ref "DOV3") (pin "A") (pinfunction "A_A") (pintype "passive"))
      (node (ref "J_BATT/GND") (pin "1") (pinfunction "1_1") (pintype "passive"))
      (node (ref "J_BATT/GND") (pin "2") (pinfunction "2_2") (pintype "passive"))
      (node (ref "J_BATT/GND") (pin "3") (pinfunction "3_3") (pintype "passive"))
      (node (ref "J_BATT/GND") (pin "4") (pinfunction "4_4") (pintype "passive"))
      (node (ref "QA_H5") (pin "2") (pinfunction "D_2") (pintype "bidirectional"))
      (node (ref "QA_H6") (pin "2") (pinfunction "D_2") (pintype "bidirectional"))
      (node (ref "RLD1") (pin "2") (pinfunction "2_2") (pintype "passive"))
    )
    (net (code "23") (name "VSS_A") (class "Default")
      (node (ref "CBOOT1") (pin "2") (pinfunction "2_2") (pintype "passive"))
      (node (ref "DOV4") (pin "A") (pinfunction "A_A") (pintype "passive"))
      (node (ref "DRVR_X") (pin "6") (pinfunction "6/BRIDGE_6") (pintype "bidirectional"))
      (node (ref "DZ15V2") (pin "2") (pinfunction "A_2") (pintype "passive"))
      (node (ref "J_-VLOAD") (pin "1") (pinfunction "1_1") (pintype "passive"))
      (node (ref "J_-VLOAD") (pin "2") (pinfunction "2_2") (pintype "passive"))
      (node (ref "J_-VLOAD") (pin "3") (pinfunction "3_3") (pintype "passive"))
      (node (ref "J_-VLOAD") (pin "4") (pinfunction "4_4") (pintype "passive"))
      (node (ref "QA_H5") (pin "3") (pinfunction "S_3") (pintype "bidirectional"))
      (node (ref "QA_H6") (pin "3") (pinfunction "S_3") (pintype "bidirectional"))
      (node (ref "QA_L5") (pin "2") (pinfunction "D_2") (pintype "bidirectional"))
      (node (ref "QA_L6") (pin "2") (pinfunction "D_2") (pintype "bidirectional"))
      (node (ref "RGS7") (pin "2") (pinfunction "2_2") (pintype "passive"))
      (node (ref "RGS8") (pin "2") (pinfunction "2_2") (pintype "passive"))
      (node (ref "SRC1") (pin "P$1") (pinfunction "P$1_P$1") (pintype "bidirectional"))
    )
    (net (code "24") (name "unconnected-(J_-VLOAD-Pad5)") (class "Default")
      (node (ref "J_-VLOAD") (pin "5") (pinfunction "5_5") (pintype "passive"))
    )
    (net (code "25") (name "unconnected-(J_-VLOAD-Pad6)") (class "Default")
      (node (ref "J_-VLOAD") (pin "6") (pinfunction "6_6") (pintype "passive"))
    )
    (net (code "26") (name "unconnected-(J_-VLOAD-Pad7)") (class "Default")
      (node (ref "J_-VLOAD") (pin "7") (pinfunction "7_7") (pintype "passive"))
    )
    (net (code "27") (name "unconnected-(J_-VLOAD-Pad8)") (class "Default")
      (node (ref "J_-VLOAD") (pin "8") (pinfunction "8_8") (pintype "passive"))
    )
    (net (code "28") (name "unconnected-(J_BATT/GND-Pad5)") (class "Default")
      (node (ref "J_BATT/GND") (pin "5") (pinfunction "5_5") (pintype "passive"))
    )
    (net (code "29") (name "unconnected-(J_BATT/GND-Pad6)") (class "Default")
      (node (ref "J_BATT/GND") (pin "6") (pinfunction "6_6") (pintype "passive"))
    )
    (net (code "30") (name "unconnected-(MS1-Pad1)") (class "Default")
      (node (ref "MS1") (pin "1") (pinfunction "1_1") (pintype "passive"))
    )
    (net (code "31") (name "unconnected-(MS2-Pad1)") (class "Default")
      (node (ref "MS2") (pin "1") (pinfunction "1_1") (pintype "passive"))
    )
    (net (code "32") (name "unconnected-(MS3-Pad1)") (class "Default")
      (node (ref "MS3") (pin "1") (pinfunction "1_1") (pintype "passive"))
    )
  )
)
